# cartucho_throwhole.net
KiCad netlist of a schematic drawn in EAGLE
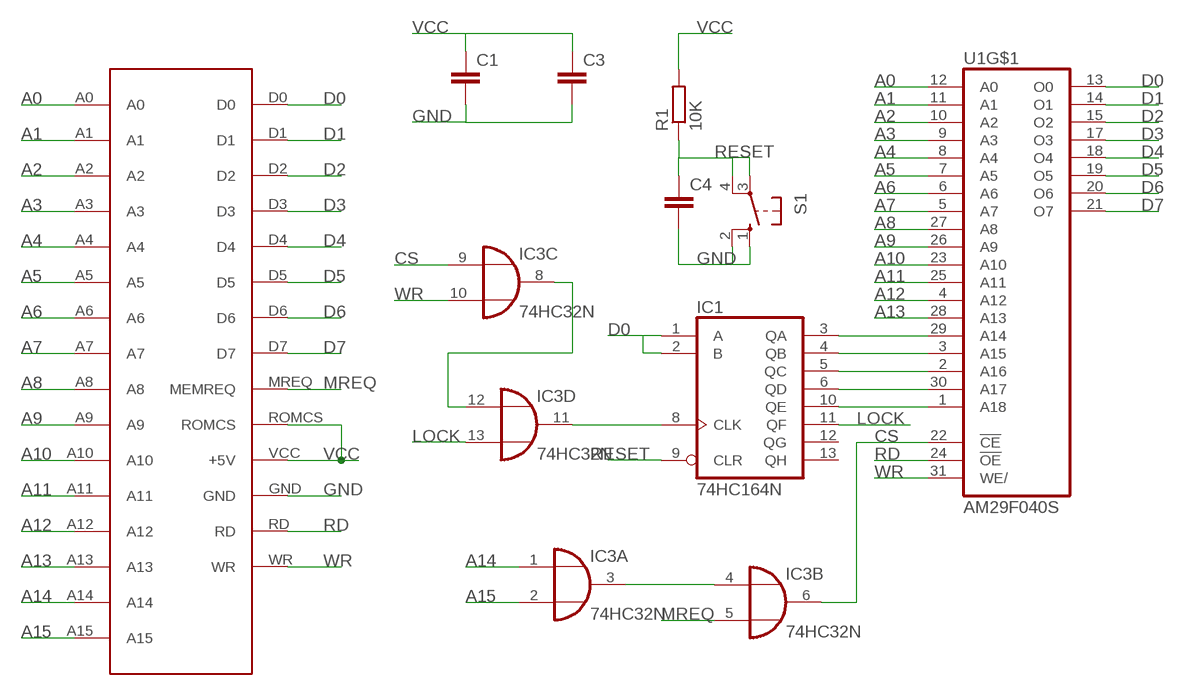
[diagram p0: schematic, sheet 1]

(export (version "E")
  (design (tool "Eeschema 10.0.6"))
  (components
    (comp (ref "C1")
      (value "C-EU050-025X075")
      (footprint "eagle-import:C050-025X075")
      (libsource (lib "eagle-import") (part "C-EU050-025X075"))
    )
    (comp (ref "C3")
      (value "C-EU050-025X075")
      (footprint "eagle-import:C050-025X075")
      (libsource (lib "eagle-import") (part "C-EU050-025X075"))
    )
    (comp (ref "C4")
      (value "C-EU050-025X075")
      (footprint "eagle-import:C050-025X075")
      (libsource (lib "eagle-import") (part "C-EU050-025X075"))
    )
    (comp (ref "IC1")
      (value "74HC164N")
      (footprint "eagle-import:DIL14")
      (libsource (lib "eagle-import") (part "74164NHC"))
    )
    (comp (ref "IC3")
      (value "74HC32N")
      (footprint "eagle-import:DIL14")
      (libsource (lib "eagle-import") (part "7432NHC"))
    )
    (comp (ref "R1")
      (value "10K")
      (footprint "eagle-import:0204_7")
      (libsource (lib "eagle-import") (part "R-EU_0204/7"))
    )
    (comp (ref "S1")
      (value "10-XX")
      (footprint "eagle-import:B3F-10XX")
      (fields (field (name "MPN") "B3F-1000"))
      (libsource (lib "eagle-import") (part "10-XX"))
    )
    (comp (ref "U$1")
      (value "IF2BUS")
      (footprint "eagle-import:BUS_CARTUCHO_IF2")
      (libsource (lib "eagle-import") (part "IF2BUS"))
    )
    (comp (ref "U1")
      (value "AM29F040S")
      (footprint "eagle-import:PLCC-SR32")
      (libsource (lib "eagle-import") (part "AM29F040S"))
    )
  )
  (nets
    (net (code "1") (name "/A0") (class "Default")
      (node (ref "U$1") (pin "A0") (pinfunction "A0_A0") (pintype "bidirectional"))
      (node (ref "U1") (pin "12") (pinfunction "A0_12") (pintype "input"))
    )
    (net (code "2") (name "/A1") (class "Default")
      (node (ref "U$1") (pin "A1") (pinfunction "A1_A1") (pintype "bidirectional"))
      (node (ref "U1") (pin "11") (pinfunction "A1_11") (pintype "input"))
    )
    (net (code "3") (name "/A2") (class "Default")
      (node (ref "U$1") (pin "A2") (pinfunction "A2_A2") (pintype "bidirectional"))
      (node (ref "U1") (pin "10") (pinfunction "A2_10") (pintype "input"))
    )
    (net (code "4") (name "/A3") (class "Default")
      (node (ref "U$1") (pin "A3") (pinfunction "A3_A3") (pintype "bidirectional"))
      (node (ref "U1") (pin "9") (pinfunction "A3_9") (pintype "input"))
    )
    (net (code "5") (name "/A4") (class "Default")
      (node (ref "U$1") (pin "A4") (pinfunction "A4_A4") (pintype "bidirectional"))
      (node (ref "U1") (pin "8") (pinfunction "A4_8") (pintype "input"))
    )
    (net (code "6") (name "/A5") (class "Default")
      (node (ref "U$1") (pin "A5") (pinfunction "A5_A5") (pintype "bidirectional"))
      (node (ref "U1") (pin "7") (pinfunction "A5_7") (pintype "input"))
    )
    (net (code "7") (name "/A6") (class "Default")
      (node (ref "U$1") (pin "A6") (pinfunction "A6_A6") (pintype "bidirectional"))
      (node (ref "U1") (pin "6") (pinfunction "A6_6") (pintype "input"))
    )
    (net (code "8") (name "/A7") (class "Default")
      (node (ref "U$1") (pin "A7") (pinfunction "A7_A7") (pintype "bidirectional"))
      (node (ref "U1") (pin "5") (pinfunction "A7_5") (pintype "input"))
    )
    (net (code "9") (name "/A8") (class "Default")
      (node (ref "U$1") (pin "A8") (pinfunction "A8_A8") (pintype "bidirectional"))
      (node (ref "U1") (pin "27") (pinfunction "A8_27") (pintype "input"))
    )
    (net (code "10") (name "/A9") (class "Default")
      (node (ref "U$1") (pin "A9") (pinfunction "A9_A9") (pintype "bidirectional"))
      (node (ref "U1") (pin "26") (pinfunction "A9_26") (pintype "input"))
    )
    (net (code "11") (name "/A10") (class "Default")
      (node (ref "U$1") (pin "A10") (pinfunction "A10_A10") (pintype "bidirectional"))
      (node (ref "U1") (pin "23") (pinfunction "A10_23") (pintype "input"))
    )
    (net (code "12") (name "/A11") (class "Default")
      (node (ref "U$1") (pin "A11") (pinfunction "A11_A11") (pintype "bidirectional"))
      (node (ref "U1") (pin "25") (pinfunction "A11_25") (pintype "input"))
    )
    (net (code "13") (name "/A12") (class "Default")
      (node (ref "U$1") (pin "A12") (pinfunction "A12_A12") (pintype "bidirectional"))
      (node (ref "U1") (pin "4") (pinfunction "A12_4") (pintype "input"))
    )
    (net (code "14") (name "/A13") (class "Default")
      (node (ref "U$1") (pin "A13") (pinfunction "A13_A13") (pintype "bidirectional"))
      (node (ref "U1") (pin "28") (pinfunction "A13_28") (pintype "input"))
    )
    (net (code "15") (name "/A14") (class "Default")
      (node (ref "IC3") (pin "1") (pinfunction "I0_1") (pintype "input"))
      (node (ref "U$1") (pin "A14") (pinfunction "A14_A14") (pintype "bidirectional"))
    )
    (net (code "16") (name "/A15") (class "Default")
      (node (ref "IC3") (pin "2") (pinfunction "I1_2") (pintype "input"))
      (node (ref "U$1") (pin "A15") (pinfunction "A15_A15") (pintype "bidirectional"))
    )
    (net (code "17") (name "/CS") (class "Default")
      (node (ref "IC3") (pin "6") (pinfunction "O_6") (pintype "output"))
      (node (ref "IC3") (pin "9") (pinfunction "I0_9") (pintype "input"))
      (node (ref "U1") (pin "22") (pinfunction "~{CE}_22") (pintype "input"))
    )
    (net (code "18") (name "/D0") (class "Default")
      (node (ref "IC1") (pin "1") (pinfunction "A_1") (pintype "input"))
      (node (ref "IC1") (pin "2") (pinfunction "B_2") (pintype "input"))
      (node (ref "U$1") (pin "D0") (pinfunction "D0_D0") (pintype "bidirectional"))
      (node (ref "U1") (pin "13") (pinfunction "O0_13") (pintype "tri_state"))
    )
    (net (code "19") (name "/D1") (class "Default")
      (node (ref "U$1") (pin "D1") (pinfunction "D1_D1") (pintype "bidirectional"))
      (node (ref "U1") (pin "14") (pinfunction "O1_14") (pintype "tri_state"))
    )
    (net (code "20") (name "/D2") (class "Default")
      (node (ref "U$1") (pin "D2") (pinfunction "D2_D2") (pintype "bidirectional"))
      (node (ref "U1") (pin "15") (pinfunction "O2_15") (pintype "tri_state"))
    )
    (net (code "21") (name "/D3") (class "Default")
      (node (ref "U$1") (pin "D3") (pinfunction "D3_D3") (pintype "bidirectional"))
      (node (ref "U1") (pin "17") (pinfunction "O3_17") (pintype "tri_state"))
    )
    (net (code "22") (name "/D4") (class "Default")
      (node (ref "U$1") (pin "D4") (pinfunction "D4_D4") (pintype "bidirectional"))
      (node (ref "U1") (pin "18") (pinfunction "O4_18") (pintype "tri_state"))
    )
    (net (code "23") (name "/D5") (class "Default")
      (node (ref "U$1") (pin "D5") (pinfunction "D5_D5") (pintype "bidirectional"))
      (node (ref "U1") (pin "19") (pinfunction "O5_19") (pintype "tri_state"))
    )
    (net (code "24") (name "/D6") (class "Default")
      (node (ref "U$1") (pin "D6") (pinfunction "D6_D6") (pintype "bidirectional"))
      (node (ref "U1") (pin "20") (pinfunction "O6_20") (pintype "tri_state"))
    )
    (net (code "25") (name "/D7") (class "Default")
      (node (ref "U$1") (pin "D7") (pinfunction "D7_D7") (pintype "bidirectional"))
      (node (ref "U1") (pin "21") (pinfunction "O7_21") (pintype "tri_state"))
    )
    (net (code "26") (name "/GND") (class "Default")
      (node (ref "C1") (pin "2") (pinfunction "2_2") (pintype "passive"))
      (node (ref "C3") (pin "2") (pinfunction "2_2") (pintype "passive"))
      (node (ref "C4") (pin "2") (pinfunction "2_2") (pintype "passive"))
      (node (ref "S1") (pin "1") (pinfunction "S_1") (pintype "passive"))
      (node (ref "S1") (pin "2") (pinfunction "S1_2") (pintype "passive"))
      (node (ref "U$1") (pin "GND") (pinfunction "GND_GND") (pintype "bidirectional"))
    )
    (net (code "27") (name "/LOCK") (class "Default")
      (node (ref "IC1") (pin "11") (pinfunction "QF_11") (pintype "output"))
      (node (ref "IC3") (pin "13") (pinfunction "I1_13") (pintype "input"))
    )
    (net (code "28") (name "/MREQ") (class "Default")
      (node (ref "IC3") (pin "5") (pinfunction "I1_5") (pintype "input"))
      (node (ref "U$1") (pin "MREQ") (pinfunction "MEMREQ_MREQ") (pintype "bidirectional"))
    )
    (net (code "29") (name "/RD") (class "Default")
      (node (ref "U$1") (pin "RD") (pinfunction "RD_RD") (pintype "bidirectional"))
      (node (ref "U1") (pin "24") (pinfunction "~{OE}_24") (pintype "input"))
    )
    (net (code "30") (name "/RESET") (class "Default")
      (node (ref "C4") (pin "1") (pinfunction "1_1") (pintype "passive"))
      (node (ref "IC1") (pin "9") (pinfunction "CLR_9") (pintype "input"))
      (node (ref "R1") (pin "1") (pinfunction "1_1") (pintype "passive"))
      (node (ref "S1") (pin "3") (pinfunction "P_3") (pintype "passive"))
      (node (ref "S1") (pin "4") (pinfunction "P1_4") (pintype "passive"))
    )
    (net (code "31") (name "/VCC") (class "Default")
      (node (ref "C1") (pin "1") (pinfunction "1_1") (pintype "passive"))
      (node (ref "C3") (pin "1") (pinfunction "1_1") (pintype "passive"))
      (node (ref "R1") (pin "2") (pinfunction "2_2") (pintype "passive"))
      (node (ref "U$1") (pin "ROMCS") (pinfunction "ROMCS_ROMCS") (pintype "bidirectional"))
      (node (ref "U$1") (pin "VCC") (pinfunction "+5V_VCC") (pintype "bidirectional"))
    )
    (net (code "32") (name "/WR") (class "Default")
      (node (ref "IC3") (pin "10") (pinfunction "I1_10") (pintype "input"))
      (node (ref "U$1") (pin "WR") (pinfunction "WR_WR") (pintype "bidirectional"))
      (node (ref "U1") (pin "31") (pinfunction "WE/_31") (pintype "input"))
    )
    (net (code "33") (name "Net-(IC1A-CLK)") (class "Default")
      (node (ref "IC1") (pin "8") (pinfunction "CLK_8") (pintype "input"))
      (node (ref "IC3") (pin "11") (pinfunction "O_11") (pintype "output"))
    )
    (net (code "34") (name "Net-(IC1A-QA)") (class "Default")
      (node (ref "IC1") (pin "3") (pinfunction "QA_3") (pintype "output"))
      (node (ref "U1") (pin "29") (pinfunction "A14_29") (pintype "input"))
    )
    (net (code "35") (name "Net-(IC1A-QB)") (class "Default")
      (node (ref "IC1") (pin "4") (pinfunction "QB_4") (pintype "output"))
      (node (ref "U1") (pin "3") (pinfunction "A15_3") (pintype "input"))
    )
    (net (code "36") (name "Net-(IC1A-QC)") (class "Default")
      (node (ref "IC1") (pin "5") (pinfunction "QC_5") (pintype "output"))
      (node (ref "U1") (pin "2") (pinfunction "A16_2") (pintype "input"))
    )
    (net (code "37") (name "Net-(IC1A-QD)") (class "Default")
      (node (ref "IC1") (pin "6") (pinfunction "QD_6") (pintype "output"))
      (node (ref "U1") (pin "30") (pinfunction "A17_30") (pintype "input"))
    )
    (net (code "38") (name "Net-(IC1A-QE)") (class "Default")
      (node (ref "IC1") (pin "10") (pinfunction "QE_10") (pintype "output"))
      (node (ref "U1") (pin "1") (pinfunction "A18_1") (pintype "input"))
    )
    (net (code "39") (name "Net-(IC3A-O)") (class "Default")
      (node (ref "IC3") (pin "3") (pinfunction "O_3") (pintype "output"))
      (node (ref "IC3") (pin "4") (pinfunction "I0_4") (pintype "input"))
    )
    (net (code "40") (name "Net-(IC3C-O)") (class "Default")
      (node (ref "IC3") (pin "12") (pinfunction "I0_12") (pintype "input"))
      (node (ref "IC3") (pin "8") (pinfunction "O_8") (pintype "output"))
    )
    (net (code "41") (name "unconnected-(IC1A-QG-Pad12)") (class "Default")
      (node (ref "IC1") (pin "12") (pinfunction "QG_12") (pintype "output"))
    )
    (net (code "42") (name "unconnected-(IC1A-QH-Pad13)") (class "Default")
      (node (ref "IC1") (pin "13") (pinfunction "QH_13") (pintype "output"))
    )
  )
)
